# 32nbIoT.net
KiCad netlist of a schematic drawn in EAGLE
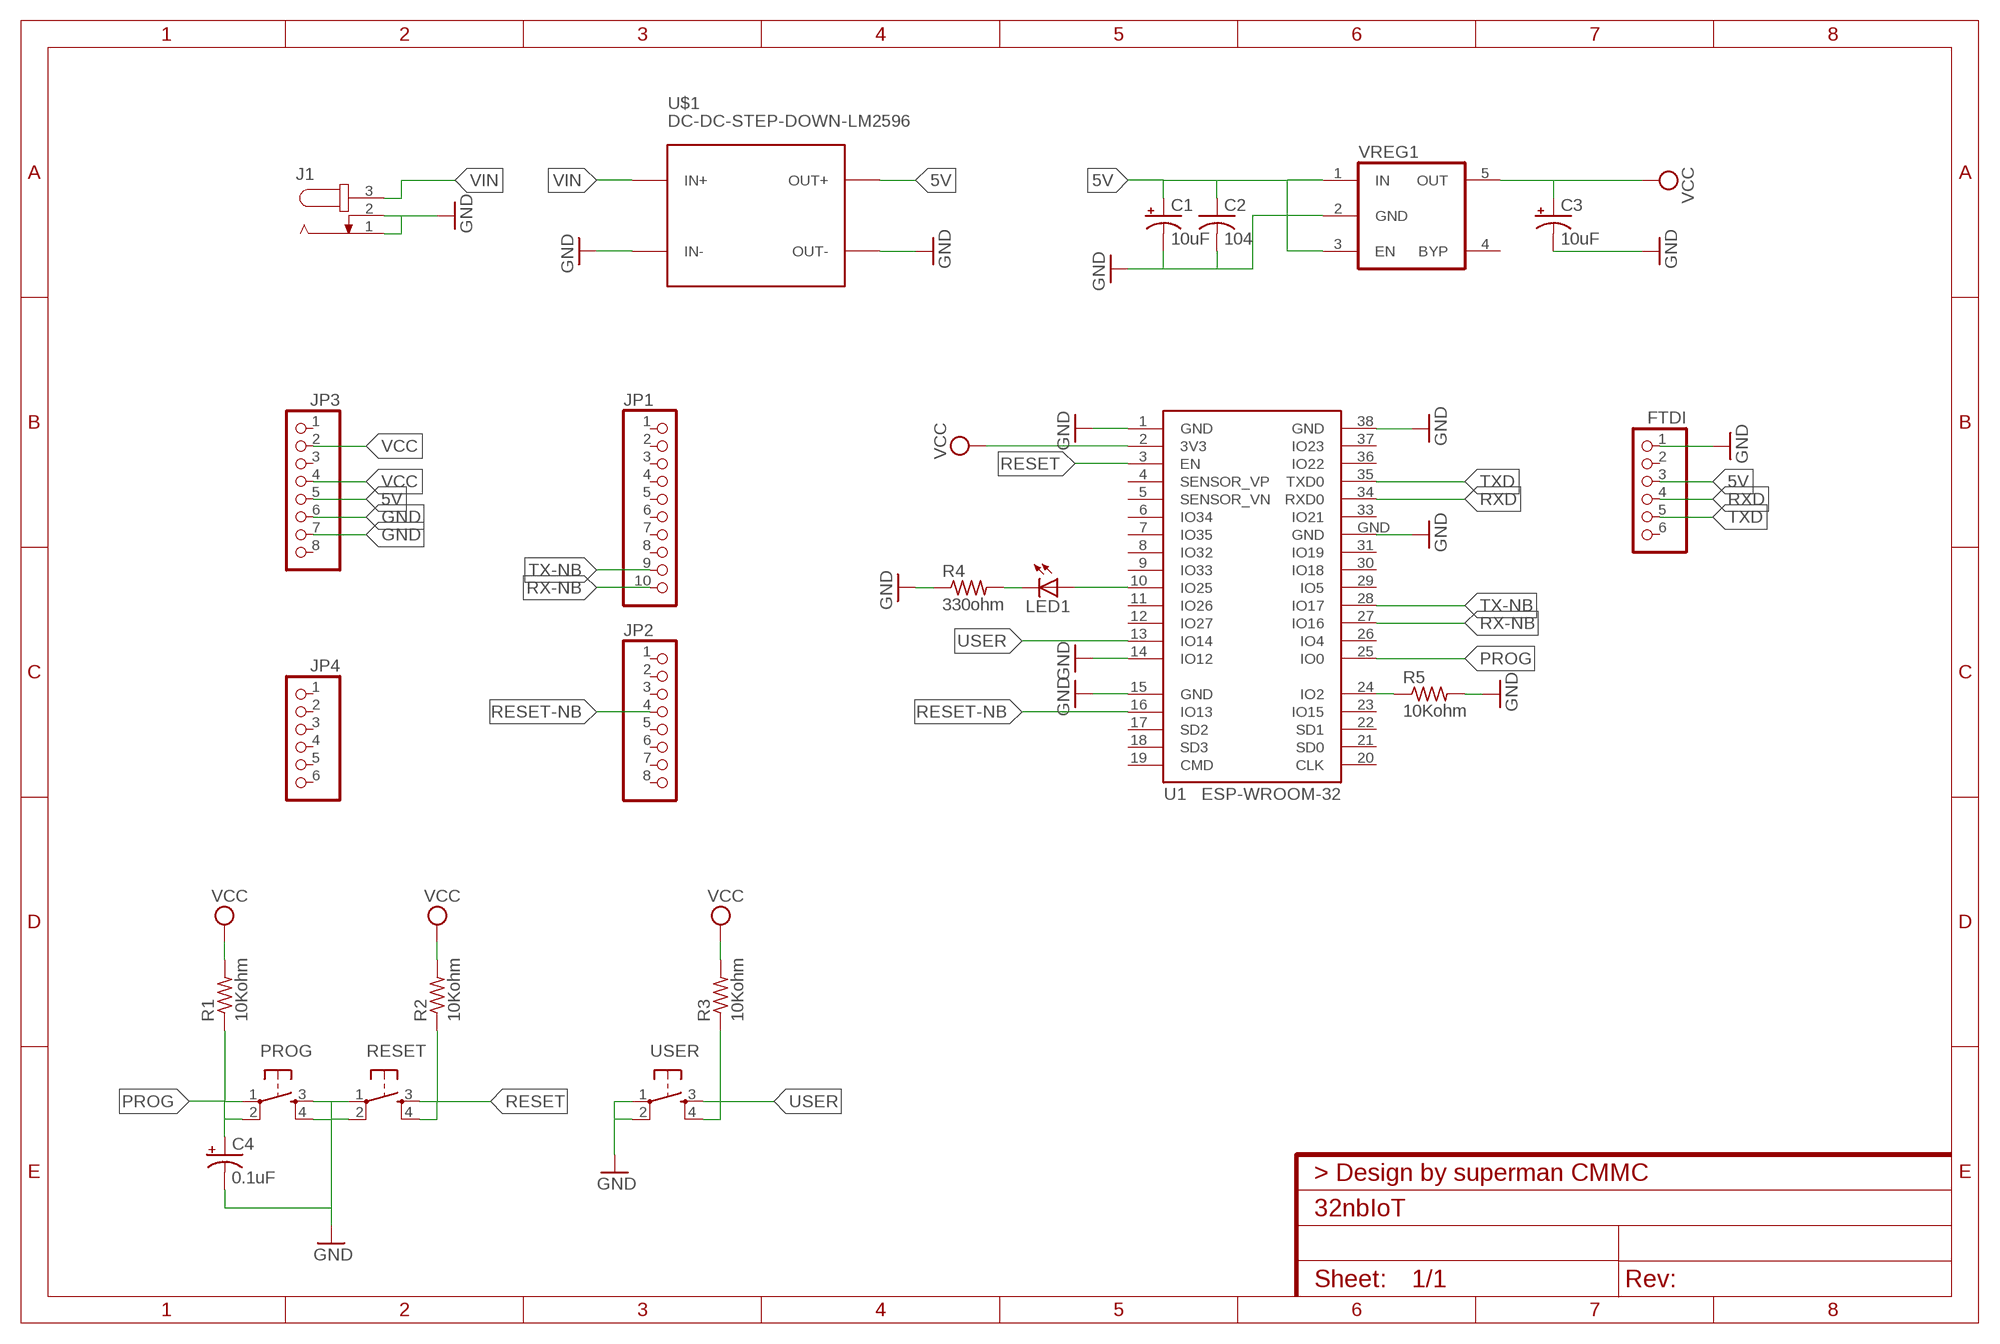
[diagram p0: schematic, sheet 1]

(export (version "E")
  (design (tool "Eeschema 10.0.6"))
  (components
    (comp (ref "C1")
      (value "10uF")
      (footprint "eagle-import:E2,5-6")
      (libsource (lib "eagle-import") (part "CPOL-USE2.5-6"))
    )
    (comp (ref "C2")
      (value "104")
      (footprint "eagle-import:C050-024X044")
      (libsource (lib "eagle-import") (part "C-US050-024X044"))
    )
    (comp (ref "C3")
      (value "10uF")
      (footprint "eagle-import:E2,5-6")
      (libsource (lib "eagle-import") (part "CPOL-USE2.5-6"))
    )
    (comp (ref "C4")
      (value "0.1uF")
      (footprint "eagle-import:E2,5-6")
      (libsource (lib "eagle-import") (part "CPOL-USE2.5-6"))
    )
    (comp (ref "FTDI")
      (value "PINHD-1X6")
      (footprint "eagle-import:1X06")
      (libsource (lib "eagle-import") (part "PINHD-1X6"))
    )
    (comp (ref "J1")
      (value "JACK-PLUG1")
      (footprint "eagle-import:SPC4078")
      (libsource (lib "eagle-import") (part "JACK-PLUG1"))
    )
    (comp (ref "JP1")
      (value "PINHD-1X10")
      (footprint "eagle-import:1X10")
      (libsource (lib "eagle-import") (part "PINHD-1X10"))
    )
    (comp (ref "JP2")
      (value "PINHD-1X8")
      (footprint "eagle-import:1X08")
      (libsource (lib "eagle-import") (part "PINHD-1X8"))
    )
    (comp (ref "JP3")
      (value "PINHD-1X8")
      (footprint "eagle-import:1X08")
      (libsource (lib "eagle-import") (part "PINHD-1X8"))
    )
    (comp (ref "JP4")
      (value "PINHD-1X6")
      (footprint "eagle-import:1X06")
      (libsource (lib "eagle-import") (part "pinhead_325_PINHD-1X6"))
    )
    (comp (ref "LED1")
      (value "LED5MM")
      (footprint "eagle-import:LED5MM")
      (libsource (lib "eagle-import") (part "LED5MM"))
    )
    (comp (ref "PROG")
      (value "TAC_SWITCHPTH")
      (footprint "eagle-import:TACTILE-PTH")
      (libsource (lib "eagle-import") (part "TAC_SWITCHPTH"))
    )
    (comp (ref "R1")
      (value "10Kohm")
      (footprint "eagle-import:0207_10")
      (libsource (lib "eagle-import") (part "R-US_0207/10"))
    )
    (comp (ref "R2")
      (value "10Kohm")
      (footprint "eagle-import:0207_10")
      (libsource (lib "eagle-import") (part "R-US_0207/10"))
    )
    (comp (ref "R3")
      (value "10Kohm")
      (footprint "eagle-import:0207_10")
      (libsource (lib "eagle-import") (part "R-US_0207/10"))
    )
    (comp (ref "R4")
      (value "330ohm")
      (footprint "eagle-import:0207_10")
      (libsource (lib "eagle-import") (part "R-US_0207/10"))
    )
    (comp (ref "R5")
      (value "10Kohm")
      (footprint "eagle-import:0207_10")
      (libsource (lib "eagle-import") (part "R-US_0207/10"))
    )
    (comp (ref "RESET")
      (value "TAC_SWITCHPTH")
      (footprint "eagle-import:TACTILE-PTH")
      (libsource (lib "eagle-import") (part "TAC_SWITCHPTH"))
    )
    (comp (ref "U$1")
      (value "DC-DC-STEP-DOWN-LM2596")
      (footprint "eagle-import:DC-DC-STEP-DOWN-LM2596")
      (libsource (lib "eagle-import") (part "DC-DC-STEP-DOWN-LM2596"))
    )
    (comp (ref "U1")
      (value "ESP-WROOM-32")
      (footprint "eagle-import:ESP-WROOM-32")
      (libsource (lib "eagle-import") (part "ESP-WROOM-32"))
    )
    (comp (ref "USER")
      (value "TAC_SWITCHPTH")
      (footprint "eagle-import:TACTILE-PTH")
      (libsource (lib "eagle-import") (part "TAC_SWITCHPTH"))
    )
    (comp (ref "VREG1")
      (value "VREG_5PINS-SOT-23-5")
      (footprint "eagle-import:SOT-23-5")
      (libsource (lib "eagle-import") (part "VREG_5PINS-SOT-23-5"))
    )
  )
  (nets
    (net (code "1") (name "5V") (class "Default")
      (node (ref "C1") (pin "+") (pinfunction "+_+") (pintype "passive"))
      (node (ref "C2") (pin "1") (pinfunction "1_1") (pintype "passive"))
      (node (ref "FTDI") (pin "3") (pinfunction "3_3") (pintype "passive"))
      (node (ref "JP3") (pin "5") (pinfunction "5_5") (pintype "passive"))
      (node (ref "U$1") (pin "OUT+") (pinfunction "OUT+_OUT+") (pintype "bidirectional"))
      (node (ref "VREG1") (pin "1") (pinfunction "IN_1") (pintype "bidirectional"))
      (node (ref "VREG1") (pin "3") (pinfunction "EN_3") (pintype "bidirectional"))
    )
    (net (code "2") (name "GND") (class "Default")
      (node (ref "C1") (pin "-") (pinfunction "-_-") (pintype "passive"))
      (node (ref "C2") (pin "2") (pinfunction "2_2") (pintype "passive"))
      (node (ref "C3") (pin "-") (pinfunction "-_-") (pintype "passive"))
      (node (ref "C4") (pin "-") (pinfunction "-_-") (pintype "passive"))
      (node (ref "FTDI") (pin "1") (pinfunction "1_1") (pintype "passive"))
      (node (ref "J1") (pin "1") (pinfunction "1_1") (pintype "passive"))
      (node (ref "J1") (pin "2") (pinfunction "2_2") (pintype "passive"))
      (node (ref "JP3") (pin "6") (pinfunction "6_6") (pintype "passive"))
      (node (ref "JP3") (pin "7") (pinfunction "7_7") (pintype "passive"))
      (node (ref "PROG") (pin "3") (pinfunction "3_3") (pintype "passive"))
      (node (ref "PROG") (pin "4") (pinfunction "4_4") (pintype "passive"))
      (node (ref "R4") (pin "1") (pinfunction "1_1") (pintype "passive"))
      (node (ref "R5") (pin "2") (pinfunction "2_2") (pintype "passive"))
      (node (ref "RESET") (pin "1") (pinfunction "1_1") (pintype "passive"))
      (node (ref "RESET") (pin "2") (pinfunction "2_2") (pintype "passive"))
      (node (ref "U$1") (pin "IN-") (pinfunction "IN-_IN-") (pintype "bidirectional"))
      (node (ref "U$1") (pin "OUT-") (pinfunction "OUT-_OUT-") (pintype "bidirectional"))
      (node (ref "U1") (pin "1") (pinfunction "GND_1") (pintype "power_in"))
      (node (ref "U1") (pin "14") (pinfunction "IO12_14") (pintype "bidirectional"))
      (node (ref "U1") (pin "15") (pinfunction "GND_15") (pintype "power_in"))
      (node (ref "U1") (pin "38") (pinfunction "GND_38") (pintype "power_in"))
      (node (ref "U1") (pin "GND") (pinfunction "GND_GND") (pintype "power_in"))
      (node (ref "USER") (pin "1") (pinfunction "1_1") (pintype "passive"))
      (node (ref "USER") (pin "2") (pinfunction "2_2") (pintype "passive"))
      (node (ref "VREG1") (pin "2") (pinfunction "GND_2") (pintype "bidirectional"))
    )
    (net (code "3") (name "Net-(LED1-C)") (class "Default")
      (node (ref "LED1") (pin "K") (pinfunction "C_K") (pintype "passive"))
      (node (ref "R4") (pin "2") (pinfunction "2_2") (pintype "passive"))
    )
    (net (code "4") (name "Net-(U1-IO2)") (class "Default")
      (node (ref "R5") (pin "1") (pinfunction "1_1") (pintype "passive"))
      (node (ref "U1") (pin "24") (pinfunction "IO2_24") (pintype "bidirectional"))
    )
    (net (code "5") (name "Net-(U1-IO25)") (class "Default")
      (node (ref "LED1") (pin "A") (pinfunction "A_A") (pintype "passive"))
      (node (ref "U1") (pin "10") (pinfunction "IO25_10") (pintype "bidirectional"))
    )
    (net (code "6") (name "PROG") (class "Default")
      (node (ref "C4") (pin "+") (pinfunction "+_+") (pintype "passive"))
      (node (ref "PROG") (pin "1") (pinfunction "1_1") (pintype "passive"))
      (node (ref "PROG") (pin "2") (pinfunction "2_2") (pintype "passive"))
      (node (ref "R1") (pin "1") (pinfunction "1_1") (pintype "passive"))
      (node (ref "U1") (pin "25") (pinfunction "IO0_25") (pintype "bidirectional"))
    )
    (net (code "7") (name "RESET") (class "Default")
      (node (ref "R2") (pin "1") (pinfunction "1_1") (pintype "passive"))
      (node (ref "RESET") (pin "3") (pinfunction "3_3") (pintype "passive"))
      (node (ref "RESET") (pin "4") (pinfunction "4_4") (pintype "passive"))
      (node (ref "U1") (pin "3") (pinfunction "EN_3") (pintype "input"))
    )
    (net (code "8") (name "RESET-NB") (class "Default")
      (node (ref "JP2") (pin "4") (pinfunction "4_4") (pintype "passive"))
      (node (ref "U1") (pin "16") (pinfunction "IO13_16") (pintype "bidirectional"))
    )
    (net (code "9") (name "RX-NB") (class "Default")
      (node (ref "JP1") (pin "10") (pinfunction "10_10") (pintype "passive"))
      (node (ref "U1") (pin "27") (pinfunction "IO16_27") (pintype "bidirectional"))
    )
    (net (code "10") (name "RXD") (class "Default")
      (node (ref "FTDI") (pin "4") (pinfunction "4_4") (pintype "passive"))
      (node (ref "U1") (pin "34") (pinfunction "RXD0_34") (pintype "bidirectional"))
    )
    (net (code "11") (name "TX-NB") (class "Default")
      (node (ref "JP1") (pin "9") (pinfunction "9_9") (pintype "passive"))
      (node (ref "U1") (pin "28") (pinfunction "IO17_28") (pintype "bidirectional"))
    )
    (net (code "12") (name "TXD") (class "Default")
      (node (ref "FTDI") (pin "5") (pinfunction "5_5") (pintype "passive"))
      (node (ref "U1") (pin "35") (pinfunction "TXD0_35") (pintype "bidirectional"))
    )
    (net (code "13") (name "USER") (class "Default")
      (node (ref "R3") (pin "1") (pinfunction "1_1") (pintype "passive"))
      (node (ref "U1") (pin "13") (pinfunction "IO14_13") (pintype "bidirectional"))
      (node (ref "USER") (pin "3") (pinfunction "3_3") (pintype "passive"))
      (node (ref "USER") (pin "4") (pinfunction "4_4") (pintype "passive"))
    )
    (net (code "14") (name "VCC") (class "Default")
      (node (ref "C3") (pin "+") (pinfunction "+_+") (pintype "passive"))
      (node (ref "JP3") (pin "2") (pinfunction "2_2") (pintype "passive"))
      (node (ref "JP3") (pin "4") (pinfunction "4_4") (pintype "passive"))
      (node (ref "R1") (pin "2") (pinfunction "2_2") (pintype "passive"))
      (node (ref "R2") (pin "2") (pinfunction "2_2") (pintype "passive"))
      (node (ref "R3") (pin "2") (pinfunction "2_2") (pintype "passive"))
      (node (ref "U1") (pin "2") (pinfunction "3V3_2") (pintype "power_in"))
      (node (ref "VREG1") (pin "5") (pinfunction "OUT_5") (pintype "bidirectional"))
    )
    (net (code "15") (name "VIN") (class "Default")
      (node (ref "J1") (pin "3") (pinfunction "3_3") (pintype "passive"))
      (node (ref "U$1") (pin "IN+") (pinfunction "IN+_IN+") (pintype "bidirectional"))
    )
    (net (code "16") (name "unconnected-(FTDI-Pad2)") (class "Default")
      (node (ref "FTDI") (pin "2") (pinfunction "2_2") (pintype "passive"))
    )
    (net (code "17") (name "unconnected-(FTDI-Pad6)") (class "Default")
      (node (ref "FTDI") (pin "6") (pinfunction "6_6") (pintype "passive"))
    )
    (net (code "18") (name "unconnected-(JP1-Pad1)") (class "Default")
      (node (ref "JP1") (pin "1") (pinfunction "1_1") (pintype "passive"))
    )
    (net (code "19") (name "unconnected-(JP1-Pad2)") (class "Default")
      (node (ref "JP1") (pin "2") (pinfunction "2_2") (pintype "passive"))
    )
    (net (code "20") (name "unconnected-(JP1-Pad3)") (class "Default")
      (node (ref "JP1") (pin "3") (pinfunction "3_3") (pintype "passive"))
    )
    (net (code "21") (name "unconnected-(JP1-Pad4)") (class "Default")
      (node (ref "JP1") (pin "4") (pinfunction "4_4") (pintype "passive"))
    )
    (net (code "22") (name "unconnected-(JP1-Pad5)") (class "Default")
      (node (ref "JP1") (pin "5") (pinfunction "5_5") (pintype "passive"))
    )
    (net (code "23") (name "unconnected-(JP1-Pad6)") (class "Default")
      (node (ref "JP1") (pin "6") (pinfunction "6_6") (pintype "passive"))
    )
    (net (code "24") (name "unconnected-(JP1-Pad7)") (class "Default")
      (node (ref "JP1") (pin "7") (pinfunction "7_7") (pintype "passive"))
    )
    (net (code "25") (name "unconnected-(JP1-Pad8)") (class "Default")
      (node (ref "JP1") (pin "8") (pinfunction "8_8") (pintype "passive"))
    )
    (net (code "26") (name "unconnected-(JP2-Pad1)") (class "Default")
      (node (ref "JP2") (pin "1") (pinfunction "1_1") (pintype "passive"))
    )
    (net (code "27") (name "unconnected-(JP2-Pad2)") (class "Default")
      (node (ref "JP2") (pin "2") (pinfunction "2_2") (pintype "passive"))
    )
    (net (code "28") (name "unconnected-(JP2-Pad3)") (class "Default")
      (node (ref "JP2") (pin "3") (pinfunction "3_3") (pintype "passive"))
    )
    (net (code "29") (name "unconnected-(JP2-Pad5)") (class "Default")
      (node (ref "JP2") (pin "5") (pinfunction "5_5") (pintype "passive"))
    )
    (net (code "30") (name "unconnected-(JP2-Pad6)") (class "Default")
      (node (ref "JP2") (pin "6") (pinfunction "6_6") (pintype "passive"))
    )
    (net (code "31") (name "unconnected-(JP2-Pad7)") (class "Default")
      (node (ref "JP2") (pin "7") (pinfunction "7_7") (pintype "passive"))
    )
    (net (code "32") (name "unconnected-(JP2-Pad8)") (class "Default")
      (node (ref "JP2") (pin "8") (pinfunction "8_8") (pintype "passive"))
    )
    (net (code "33") (name "unconnected-(JP3-Pad1)") (class "Default")
      (node (ref "JP3") (pin "1") (pinfunction "1_1") (pintype "passive"))
    )
    (net (code "34") (name "unconnected-(JP3-Pad3)") (class "Default")
      (node (ref "JP3") (pin "3") (pinfunction "3_3") (pintype "passive"))
    )
    (net (code "35") (name "unconnected-(JP3-Pad8)") (class "Default")
      (node (ref "JP3") (pin "8") (pinfunction "8_8") (pintype "passive"))
    )
    (net (code "36") (name "unconnected-(JP4-Pad1)") (class "Default")
      (node (ref "JP4") (pin "1") (pinfunction "1_1") (pintype "passive"))
    )
    (net (code "37") (name "unconnected-(JP4-Pad2)") (class "Default")
      (node (ref "JP4") (pin "2") (pinfunction "2_2") (pintype "passive"))
    )
    (net (code "38") (name "unconnected-(JP4-Pad3)") (class "Default")
      (node (ref "JP4") (pin "3") (pinfunction "3_3") (pintype "passive"))
    )
    (net (code "39") (name "unconnected-(JP4-Pad4)") (class "Default")
      (node (ref "JP4") (pin "4") (pinfunction "4_4") (pintype "passive"))
    )
    (net (code "40") (name "unconnected-(JP4-Pad5)") (class "Default")
      (node (ref "JP4") (pin "5") (pinfunction "5_5") (pintype "passive"))
    )
    (net (code "41") (name "unconnected-(JP4-Pad6)") (class "Default")
      (node (ref "JP4") (pin "6") (pinfunction "6_6") (pintype "passive"))
    )
    (net (code "42") (name "unconnected-(U1-CLK-Pad20)") (class "Default")
      (node (ref "U1") (pin "20") (pinfunction "CLK_20") (pintype "bidirectional"))
    )
    (net (code "43") (name "unconnected-(U1-CMD-Pad19)") (class "Default")
      (node (ref "U1") (pin "19") (pinfunction "CMD_19") (pintype "bidirectional"))
    )
    (net (code "44") (name "unconnected-(U1-IO4-Pad26)") (class "Default")
      (node (ref "U1") (pin "26") (pinfunction "IO4_26") (pintype "bidirectional"))
    )
    (net (code "45") (name "unconnected-(U1-IO5-Pad29)") (class "Default")
      (node (ref "U1") (pin "29") (pinfunction "IO5_29") (pintype "bidirectional"))
    )
    (net (code "46") (name "unconnected-(U1-IO15-Pad23)") (class "Default")
      (node (ref "U1") (pin "23") (pinfunction "IO15_23") (pintype "bidirectional"))
    )
    (net (code "47") (name "unconnected-(U1-IO18-Pad30)") (class "Default")
      (node (ref "U1") (pin "30") (pinfunction "IO18_30") (pintype "bidirectional"))
    )
    (net (code "48") (name "unconnected-(U1-IO19-Pad31)") (class "Default")
      (node (ref "U1") (pin "31") (pinfunction "IO19_31") (pintype "bidirectional"))
    )
    (net (code "49") (name "unconnected-(U1-IO21-Pad33)") (class "Default")
      (node (ref "U1") (pin "33") (pinfunction "IO21_33") (pintype "bidirectional"))
    )
    (net (code "50") (name "unconnected-(U1-IO22-Pad36)") (class "Default")
      (node (ref "U1") (pin "36") (pinfunction "IO22_36") (pintype "bidirectional"))
    )
    (net (code "51") (name "unconnected-(U1-IO23-Pad37)") (class "Default")
      (node (ref "U1") (pin "37") (pinfunction "IO23_37") (pintype "bidirectional"))
    )
    (net (code "52") (name "unconnected-(U1-IO26-Pad11)") (class "Default")
      (node (ref "U1") (pin "11") (pinfunction "IO26_11") (pintype "bidirectional"))
    )
    (net (code "53") (name "unconnected-(U1-IO27-Pad12)") (class "Default")
      (node (ref "U1") (pin "12") (pinfunction "IO27_12") (pintype "bidirectional"))
    )
    (net (code "54") (name "unconnected-(U1-IO32-Pad8)") (class "Default")
      (node (ref "U1") (pin "8") (pinfunction "IO32_8") (pintype "bidirectional"))
    )
    (net (code "55") (name "unconnected-(U1-IO33-Pad9)") (class "Default")
      (node (ref "U1") (pin "9") (pinfunction "IO33_9") (pintype "bidirectional"))
    )
    (net (code "56") (name "unconnected-(U1-IO34-Pad6)") (class "Default")
      (node (ref "U1") (pin "6") (pinfunction "IO34_6") (pintype "bidirectional"))
    )
    (net (code "57") (name "unconnected-(U1-IO35-Pad7)") (class "Default")
      (node (ref "U1") (pin "7") (pinfunction "IO35_7") (pintype "bidirectional"))
    )
    (net (code "58") (name "unconnected-(U1-SD0-Pad21)") (class "Default")
      (node (ref "U1") (pin "21") (pinfunction "SD0_21") (pintype "bidirectional"))
    )
    (net (code "59") (name "unconnected-(U1-SD1-Pad22)") (class "Default")
      (node (ref "U1") (pin "22") (pinfunction "SD1_22") (pintype "bidirectional"))
    )
    (net (code "60") (name "unconnected-(U1-SD2-Pad17)") (class "Default")
      (node (ref "U1") (pin "17") (pinfunction "SD2_17") (pintype "bidirectional"))
    )
    (net (code "61") (name "unconnected-(U1-SD3-Pad18)") (class "Default")
      (node (ref "U1") (pin "18") (pinfunction "SD3_18") (pintype "bidirectional"))
    )
    (net (code "62") (name "unconnected-(U1-SENSOR_VN-Pad5)") (class "Default")
      (node (ref "U1") (pin "5") (pinfunction "SENSOR_VN_5") (pintype "bidirectional"))
    )
    (net (code "63") (name "unconnected-(U1-SENSOR_VP-Pad4)") (class "Default")
      (node (ref "U1") (pin "4") (pinfunction "SENSOR_VP_4") (pintype "bidirectional"))
    )
    (net (code "64") (name "unconnected-(VREG1-BYP-Pad4)") (class "Default")
      (node (ref "VREG1") (pin "4") (pinfunction "BYP_4") (pintype "bidirectional"))
    )
  )
)
